# support.net
KiCad netlist of a schematic drawn in Altium Designer
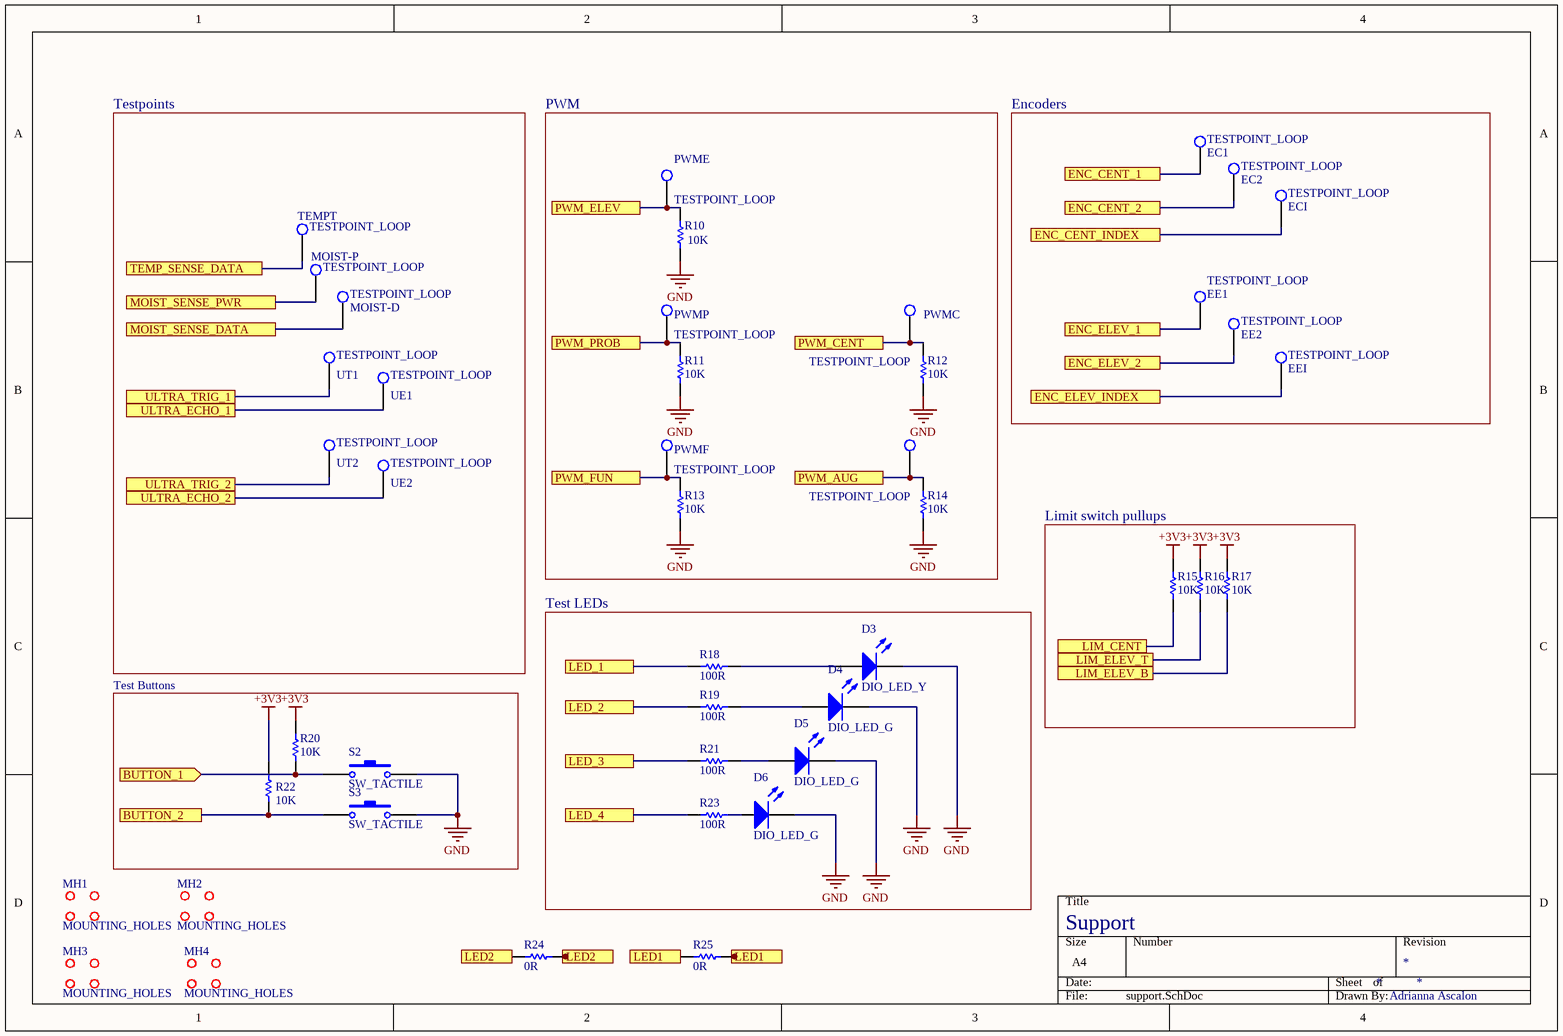
[diagram p0: support.SchDoc]

(export (version "E")
  (design (tool "Eeschema 10.0.6"))
  (components
    (comp (ref "D3")
      (value "DIO_LED_Y")
      (footprint "LED_0805_LINE")
      (description "LED YELLOW DIFFUSED 0805 SMD")
      (fields (field (name "MANUFACTURER") "OSRAM") (field (name "MPN") "LY R976-PS-36"))
      (libsource (lib "UWRT_Schematic_Library_2019") (part "DIO_LED_Y"))
    )
    (comp (ref "D4")
      (value "DIO_LED_G")
      (footprint "LED_0805_LINE")
      (description "LED GREEN DIFFUSED 0805 SMD")
      (fields (field (name "MANUFACTURER") "OSRAM") (field (name "MPN") "LG R971-KN-1"))
      (libsource (lib "UWRT_Schematic_Library_2019") (part "DIO_LED_G"))
    )
    (comp (ref "D5")
      (value "DIO_LED_G")
      (footprint "LED_0805_LINE")
      (description "LED GREEN DIFFUSED 0805 SMD")
      (fields (field (name "MANUFACTURER") "OSRAM") (field (name "MPN") "LG R971-KN-1"))
      (libsource (lib "UWRT_Schematic_Library_2019") (part "DIO_LED_G"))
    )
    (comp (ref "D6")
      (value "DIO_LED_G")
      (footprint "LED_0805_LINE")
      (description "LED GREEN DIFFUSED 0805 SMD")
      (fields (field (name "MANUFACTURER") "OSRAM") (field (name "MPN") "LG R971-KN-1"))
      (libsource (lib "UWRT_Schematic_Library_2019") (part "DIO_LED_G"))
    )
    (comp (ref "EC1")
      (value "TESTPOINT_LOOP")
      (footprint "TESTPOINT_LOOP")
      (libsource (lib "UWRT_Schematic_Library_2019") (part "TESTPOINT_LOOP"))
    )
    (comp (ref "EC2")
      (value "TESTPOINT_LOOP")
      (footprint "TESTPOINT_LOOP")
      (libsource (lib "UWRT_Schematic_Library_2019") (part "TESTPOINT_LOOP"))
    )
    (comp (ref "ECI")
      (value "TESTPOINT_LOOP")
      (footprint "TESTPOINT_LOOP")
      (libsource (lib "UWRT_Schematic_Library_2019") (part "TESTPOINT_LOOP"))
    )
    (comp (ref "EE1")
      (value "TESTPOINT_LOOP")
      (footprint "TESTPOINT_LOOP")
      (libsource (lib "UWRT_Schematic_Library_2019") (part "TESTPOINT_LOOP"))
    )
    (comp (ref "EE2")
      (value "TESTPOINT_LOOP")
      (footprint "TESTPOINT_LOOP")
      (libsource (lib "UWRT_Schematic_Library_2019") (part "TESTPOINT_LOOP"))
    )
    (comp (ref "EEI")
      (value "TESTPOINT_LOOP")
      (footprint "TESTPOINT_LOOP")
      (libsource (lib "UWRT_Schematic_Library_2019") (part "TESTPOINT_LOOP"))
    )
    (comp (ref "MH1")
      (value "MOUNTING_HOLES")
      (footprint "MOUNTING_HOLE")
      (description "6cm x 6cm")
      (libsource (lib "UWRT_Schematic_Library_2019") (part "MOUNTING_HOLES"))
    )
    (comp (ref "MH2")
      (value "MOUNTING_HOLES")
      (footprint "MOUNTING_HOLE")
      (description "6cm x 6cm")
      (libsource (lib "UWRT_Schematic_Library_2019") (part "MOUNTING_HOLES"))
    )
    (comp (ref "MH3")
      (value "MOUNTING_HOLES")
      (footprint "MOUNTING_HOLE")
      (description "6cm x 6cm")
      (libsource (lib "UWRT_Schematic_Library_2019") (part "MOUNTING_HOLES"))
    )
    (comp (ref "MH4")
      (value "MOUNTING_HOLES")
      (footprint "MOUNTING_HOLE")
      (description "6cm x 6cm")
      (libsource (lib "UWRT_Schematic_Library_2019") (part "MOUNTING_HOLES"))
    )
    (comp (ref "MOIST-D")
      (value "TESTPOINT_LOOP")
      (footprint "TESTPOINT_LOOP")
      (libsource (lib "UWRT_Schematic_Library_2019") (part "TESTPOINT_LOOP"))
    )
    (comp (ref "MOIST-P")
      (value "TESTPOINT_LOOP")
      (footprint "TESTPOINT_LOOP")
      (libsource (lib "UWRT_Schematic_Library_2019") (part "TESTPOINT_LOOP"))
    )
    (comp (ref "PWMA")
      (value "TESTPOINT_LOOP")
      (footprint "TESTPOINT_LOOP")
      (libsource (lib "UWRT_Schematic_Library_2019") (part "TESTPOINT_LOOP"))
    )
    (comp (ref "PWMC")
      (value "TESTPOINT_LOOP")
      (footprint "TESTPOINT_LOOP")
      (libsource (lib "UWRT_Schematic_Library_2019") (part "TESTPOINT_LOOP"))
    )
    (comp (ref "PWME")
      (value "TESTPOINT_LOOP")
      (footprint "TESTPOINT_LOOP")
      (libsource (lib "UWRT_Schematic_Library_2019") (part "TESTPOINT_LOOP"))
    )
    (comp (ref "PWMF")
      (value "TESTPOINT_LOOP")
      (footprint "TESTPOINT_LOOP")
      (libsource (lib "UWRT_Schematic_Library_2019") (part "TESTPOINT_LOOP"))
    )
    (comp (ref "PWMP")
      (value "TESTPOINT_LOOP")
      (footprint "TESTPOINT_LOOP")
      (libsource (lib "UWRT_Schematic_Library_2019") (part "TESTPOINT_LOOP"))
    )
    (comp (ref "R10")
      (value "10K")
      (footprint "RESC0603(1608)_N")
      (description "RES SMD 10K OHM 5% 1/10W 0603")
      (fields (field (name "MANUFACTURER") "Yageo") (field (name "TOLERANCE") "5%"))
      (libsource (lib "UWRT_Schematic_Library_2019") (part "RES_10K_0603"))
    )
    (comp (ref "R11")
      (value "10K")
      (footprint "RESC0603(1608)_N")
      (description "RES SMD 10K OHM 5% 1/10W 0603")
      (fields (field (name "MANUFACTURER") "Yageo") (field (name "TOLERANCE") "5%"))
      (libsource (lib "UWRT_Schematic_Library_2019") (part "RES_10K_0603"))
    )
    (comp (ref "R12")
      (value "10K")
      (footprint "RESC0603(1608)_N")
      (description "RES SMD 10K OHM 5% 1/10W 0603")
      (fields (field (name "MANUFACTURER") "Yageo") (field (name "TOLERANCE") "5%"))
      (libsource (lib "UWRT_Schematic_Library_2019") (part "RES_10K_0603"))
    )
    (comp (ref "R13")
      (value "10K")
      (footprint "RESC0603(1608)_N")
      (description "RES SMD 10K OHM 5% 1/10W 0603")
      (fields (field (name "MANUFACTURER") "Yageo") (field (name "TOLERANCE") "5%"))
      (libsource (lib "UWRT_Schematic_Library_2019") (part "RES_10K_0603"))
    )
    (comp (ref "R14")
      (value "10K")
      (footprint "RESC0603(1608)_N")
      (description "RES SMD 10K OHM 5% 1/10W 0603")
      (fields (field (name "MANUFACTURER") "Yageo") (field (name "TOLERANCE") "5%"))
      (libsource (lib "UWRT_Schematic_Library_2019") (part "RES_10K_0603"))
    )
    (comp (ref "R15")
      (value "10K")
      (footprint "RESC0603(1608)_N")
      (description "RES SMD 10K OHM 5% 1/10W 0603")
      (fields (field (name "MANUFACTURER") "Yageo") (field (name "TOLERANCE") "5%"))
      (libsource (lib "UWRT_Schematic_Library_2019") (part "RES_10K_0603"))
    )
    (comp (ref "R16")
      (value "10K")
      (footprint "RESC0603(1608)_N")
      (description "RES SMD 10K OHM 5% 1/10W 0603")
      (fields (field (name "MANUFACTURER") "Yageo") (field (name "TOLERANCE") "5%"))
      (libsource (lib "UWRT_Schematic_Library_2019") (part "RES_10K_0603"))
    )
    (comp (ref "R17")
      (value "10K")
      (footprint "RESC0603(1608)_N")
      (description "RES SMD 10K OHM 5% 1/10W 0603")
      (fields (field (name "MANUFACTURER") "Yageo") (field (name "TOLERANCE") "5%"))
      (libsource (lib "UWRT_Schematic_Library_2019") (part "RES_10K_0603"))
    )
    (comp (ref "R18")
      (value "100R")
      (footprint "RESC0603(1608)_N")
      (description "RES SMD 100 OHM 1% 1/10W 0603")
      (fields (field (name "MANUFACTURER") "Yageo") (field (name "TOLERANCE") "1%"))
      (libsource (lib "UWRT_Schematic_Library_2019") (part "RES_100R_0603"))
    )
    (comp (ref "R19")
      (value "100R")
      (footprint "RESC0603(1608)_N")
      (description "RES SMD 100 OHM 1% 1/10W 0603")
      (fields (field (name "MANUFACTURER") "Yageo") (field (name "TOLERANCE") "1%"))
      (libsource (lib "UWRT_Schematic_Library_2019") (part "RES_100R_0603"))
    )
    (comp (ref "R20")
      (value "10K")
      (footprint "RESC0603(1608)_N")
      (description "RES SMD 10K OHM 5% 1/10W 0603")
      (fields (field (name "MANUFACTURER") "Yageo") (field (name "TOLERANCE") "5%"))
      (libsource (lib "UWRT_Schematic_Library_2019") (part "RES_10K_0603"))
    )
    (comp (ref "R21")
      (value "100R")
      (footprint "RESC0603(1608)_N")
      (description "RES SMD 100 OHM 1% 1/10W 0603")
      (fields (field (name "MANUFACTURER") "Yageo") (field (name "TOLERANCE") "1%"))
      (libsource (lib "UWRT_Schematic_Library_2019") (part "RES_100R_0603"))
    )
    (comp (ref "R22")
      (value "10K")
      (footprint "RESC0603(1608)_N")
      (description "RES SMD 10K OHM 5% 1/10W 0603")
      (fields (field (name "MANUFACTURER") "Yageo") (field (name "TOLERANCE") "5%"))
      (libsource (lib "UWRT_Schematic_Library_2019") (part "RES_10K_0603"))
    )
    (comp (ref "R23")
      (value "100R")
      (footprint "RESC0603(1608)_N")
      (description "RES SMD 100 OHM 1% 1/10W 0603")
      (fields (field (name "MANUFACTURER") "Yageo") (field (name "TOLERANCE") "1%"))
      (libsource (lib "UWRT_Schematic_Library_2019") (part "RES_100R_0603"))
    )
    (comp (ref "R24")
      (value "0R")
      (footprint "RESC0603(1608)_N")
      (description "RES SMD 0 OHM JUMPER 1/10W 0603")
      (fields (field (name "MANUFACTURER") "Yageo") (field (name "MPN") "RC0603JR-070RL"))
      (libsource (lib "UWRT_Schematic_Library_2019") (part "RES_0R_0603"))
    )
    (comp (ref "R25")
      (value "0R")
      (footprint "RESC0603(1608)_N")
      (description "RES SMD 0 OHM JUMPER 1/10W 0603")
      (fields (field (name "MANUFACTURER") "Yageo") (field (name "MPN") "RC0603JR-070RL"))
      (libsource (lib "UWRT_Schematic_Library_2019") (part "RES_0R_0603"))
    )
    (comp (ref "S2")
      (value "SW_TACTILE")
      (footprint "B3U-1100P")
      (description "Tactile Switch (Grey)")
      (fields (field (name "DIGIKEY PART NUMBER") "SW1021TR-ND") (field (name "MPN") "B3U-1100P"))
      (libsource (lib "UWRT_Schematic_Library_2019") (part "SW_TACTILE"))
    )
    (comp (ref "S3")
      (value "SW_TACTILE")
      (footprint "B3U-1100P")
      (description "Tactile Switch (Grey)")
      (fields (field (name "DIGIKEY PART NUMBER") "SW1021TR-ND") (field (name "MPN") "B3U-1100P"))
      (libsource (lib "UWRT_Schematic_Library_2019") (part "SW_TACTILE"))
    )
    (comp (ref "TEMPT")
      (value "TESTPOINT_LOOP")
      (footprint "TESTPOINT_LOOP")
      (libsource (lib "UWRT_Schematic_Library_2019") (part "TESTPOINT_LOOP"))
    )
    (comp (ref "UE1")
      (value "TESTPOINT_LOOP")
      (footprint "TESTPOINT_LOOP")
      (libsource (lib "UWRT_Schematic_Library_2019") (part "TESTPOINT_LOOP"))
    )
    (comp (ref "UE2")
      (value "TESTPOINT_LOOP")
      (footprint "TESTPOINT_LOOP")
      (libsource (lib "UWRT_Schematic_Library_2019") (part "TESTPOINT_LOOP"))
    )
    (comp (ref "UT1")
      (value "TESTPOINT_LOOP")
      (footprint "TESTPOINT_LOOP")
      (libsource (lib "UWRT_Schematic_Library_2019") (part "TESTPOINT_LOOP"))
    )
    (comp (ref "UT2")
      (value "TESTPOINT_LOOP")
      (footprint "TESTPOINT_LOOP")
      (libsource (lib "UWRT_Schematic_Library_2019") (part "TESTPOINT_LOOP"))
    )
  )
  (nets
    (net (code "1") (name "+3V3") (class "Default")
      (node (ref "R15") (pin "2") (pinfunction "2_2") (pintype "passive"))
      (node (ref "R16") (pin "2") (pinfunction "2_2") (pintype "passive"))
      (node (ref "R17") (pin "2") (pinfunction "2_2") (pintype "passive"))
      (node (ref "R20") (pin "2") (pinfunction "2_2") (pintype "passive"))
      (node (ref "R22") (pin "1") (pinfunction "1_1") (pintype "passive"))
    )
    (net (code "2") (name "/BUTTON_1") (class "Default")
      (node (ref "R20") (pin "1") (pinfunction "1_1") (pintype "passive"))
      (node (ref "S2") (pin "1") (pinfunction "1_1") (pintype "passive"))
    )
    (net (code "3") (name "/BUTTON_2") (class "Default")
      (node (ref "R22") (pin "2") (pinfunction "2_2") (pintype "passive"))
      (node (ref "S3") (pin "1") (pinfunction "1_1") (pintype "passive"))
    )
    (net (code "4") (name "/ENC_CENT_1") (class "Default")
      (node (ref "EC1") (pin "1") (pinfunction "=value_1") (pintype "passive"))
    )
    (net (code "5") (name "/ENC_CENT_2") (class "Default")
      (node (ref "EC2") (pin "1") (pinfunction "=value_1") (pintype "passive"))
    )
    (net (code "6") (name "/ENC_CENT_INDEX") (class "Default")
      (node (ref "ECI") (pin "1") (pinfunction "=value_1") (pintype "passive"))
    )
    (net (code "7") (name "/ENC_ELEV_1") (class "Default")
      (node (ref "EE1") (pin "1") (pinfunction "=value_1") (pintype "passive"))
    )
    (net (code "8") (name "/ENC_ELEV_2") (class "Default")
      (node (ref "EE2") (pin "1") (pinfunction "=value_1") (pintype "passive"))
    )
    (net (code "9") (name "/ENC_ELEV_INDEX") (class "Default")
      (node (ref "EEI") (pin "1") (pinfunction "=value_1") (pintype "passive"))
    )
    (net (code "10") (name "/LED1") (class "Default")
      (node (ref "R25") (pin "1") (pinfunction "1_1") (pintype "passive"))
    )
    (net (code "11") (name "/LED2") (class "Default")
      (node (ref "R24") (pin "1") (pinfunction "1_1") (pintype "passive"))
    )
    (net (code "12") (name "/LED_1") (class "Default")
      (node (ref "R18") (pin "1") (pinfunction "1_1") (pintype "passive"))
    )
    (net (code "13") (name "/LED_2") (class "Default")
      (node (ref "R19") (pin "1") (pinfunction "1_1") (pintype "passive"))
    )
    (net (code "14") (name "/LED_3") (class "Default")
      (node (ref "R21") (pin "1") (pinfunction "1_1") (pintype "passive"))
    )
    (net (code "15") (name "/LED_4") (class "Default")
      (node (ref "R23") (pin "1") (pinfunction "1_1") (pintype "passive"))
    )
    (net (code "16") (name "/LIM_CENT") (class "Default")
      (node (ref "R15") (pin "1") (pinfunction "1_1") (pintype "passive"))
    )
    (net (code "17") (name "/LIM_ELEV_B") (class "Default")
      (node (ref "R17") (pin "1") (pinfunction "1_1") (pintype "passive"))
    )
    (net (code "18") (name "/LIM_ELEV_T") (class "Default")
      (node (ref "R16") (pin "1") (pinfunction "1_1") (pintype "passive"))
    )
    (net (code "19") (name "/MOIST_SENSE_DATA") (class "Default")
      (node (ref "MOIST-D") (pin "1") (pinfunction "=value_1") (pintype "passive"))
    )
    (net (code "20") (name "/MOIST_SENSE_PWR") (class "Default")
      (node (ref "MOIST-P") (pin "1") (pinfunction "=value_1") (pintype "passive"))
    )
    (net (code "21") (name "/PWM_AUG") (class "Default")
      (node (ref "PWMA") (pin "1") (pinfunction "=value_1") (pintype "passive"))
      (node (ref "R14") (pin "2") (pinfunction "2_2") (pintype "passive"))
    )
    (net (code "22") (name "/PWM_CENT") (class "Default")
      (node (ref "PWMC") (pin "1") (pinfunction "=value_1") (pintype "passive"))
      (node (ref "R12") (pin "2") (pinfunction "2_2") (pintype "passive"))
    )
    (net (code "23") (name "/PWM_ELEV") (class "Default")
      (node (ref "PWME") (pin "1") (pinfunction "=value_1") (pintype "passive"))
      (node (ref "R10") (pin "2") (pinfunction "2_2") (pintype "passive"))
    )
    (net (code "24") (name "/PWM_FUN") (class "Default")
      (node (ref "PWMF") (pin "1") (pinfunction "=value_1") (pintype "passive"))
      (node (ref "R13") (pin "2") (pinfunction "2_2") (pintype "passive"))
    )
    (net (code "25") (name "/PWM_PROB") (class "Default")
      (node (ref "PWMP") (pin "1") (pinfunction "=value_1") (pintype "passive"))
      (node (ref "R11") (pin "2") (pinfunction "2_2") (pintype "passive"))
    )
    (net (code "26") (name "/TEMP_SENSE_DATA") (class "Default")
      (node (ref "TEMPT") (pin "1") (pinfunction "=value_1") (pintype "passive"))
    )
    (net (code "27") (name "/ULTRA_ECHO_1") (class "Default")
      (node (ref "UE1") (pin "1") (pinfunction "=value_1") (pintype "passive"))
    )
    (net (code "28") (name "/ULTRA_ECHO_2") (class "Default")
      (node (ref "UE2") (pin "1") (pinfunction "=value_1") (pintype "passive"))
    )
    (net (code "29") (name "/ULTRA_TRIG_1") (class "Default")
      (node (ref "UT1") (pin "1") (pinfunction "=value_1") (pintype "passive"))
    )
    (net (code "30") (name "/ULTRA_TRIG_2") (class "Default")
      (node (ref "UT2") (pin "1") (pinfunction "=value_1") (pintype "passive"))
    )
    (net (code "31") (name "GND") (class "Default")
      (node (ref "D3") (pin "2") (pinfunction "K_2") (pintype "passive"))
      (node (ref "D4") (pin "2") (pinfunction "K_2") (pintype "passive"))
      (node (ref "D5") (pin "2") (pinfunction "K_2") (pintype "passive"))
      (node (ref "D6") (pin "2") (pinfunction "K_2") (pintype "passive"))
      (node (ref "R10") (pin "1") (pinfunction "1_1") (pintype "passive"))
      (node (ref "R11") (pin "1") (pinfunction "1_1") (pintype "passive"))
      (node (ref "R12") (pin "1") (pinfunction "1_1") (pintype "passive"))
      (node (ref "R13") (pin "1") (pinfunction "1_1") (pintype "passive"))
      (node (ref "R14") (pin "1") (pinfunction "1_1") (pintype "passive"))
      (node (ref "S2") (pin "2") (pinfunction "2_2") (pintype "passive"))
      (node (ref "S3") (pin "2") (pinfunction "2_2") (pintype "passive"))
    )
    (net (code "32") (name "Net-(D3-A)") (class "Default")
      (node (ref "D3") (pin "1") (pinfunction "A_1") (pintype "passive"))
      (node (ref "R18") (pin "2") (pinfunction "2_2") (pintype "passive"))
    )
    (net (code "33") (name "Net-(D4-A)") (class "Default")
      (node (ref "D4") (pin "1") (pinfunction "A_1") (pintype "passive"))
      (node (ref "R19") (pin "2") (pinfunction "2_2") (pintype "passive"))
    )
    (net (code "34") (name "Net-(D5-A)") (class "Default")
      (node (ref "D5") (pin "1") (pinfunction "A_1") (pintype "passive"))
      (node (ref "R21") (pin "2") (pinfunction "2_2") (pintype "passive"))
    )
    (net (code "35") (name "Net-(D6-A)") (class "Default")
      (node (ref "D6") (pin "1") (pinfunction "A_1") (pintype "passive"))
      (node (ref "R23") (pin "2") (pinfunction "2_2") (pintype "passive"))
    )
    (net (code "36") (name "unconnected-(R24-Pad2)") (class "Default")
      (node (ref "R24") (pin "2") (pinfunction "2_2") (pintype "passive"))
    )
    (net (code "37") (name "unconnected-(R25-Pad2)") (class "Default")
      (node (ref "R25") (pin "2") (pinfunction "2_2") (pintype "passive"))
    )
  )
)
